# RoboCore_RGB_Sensor.net
KiCad netlist of a schematic drawn in EAGLE
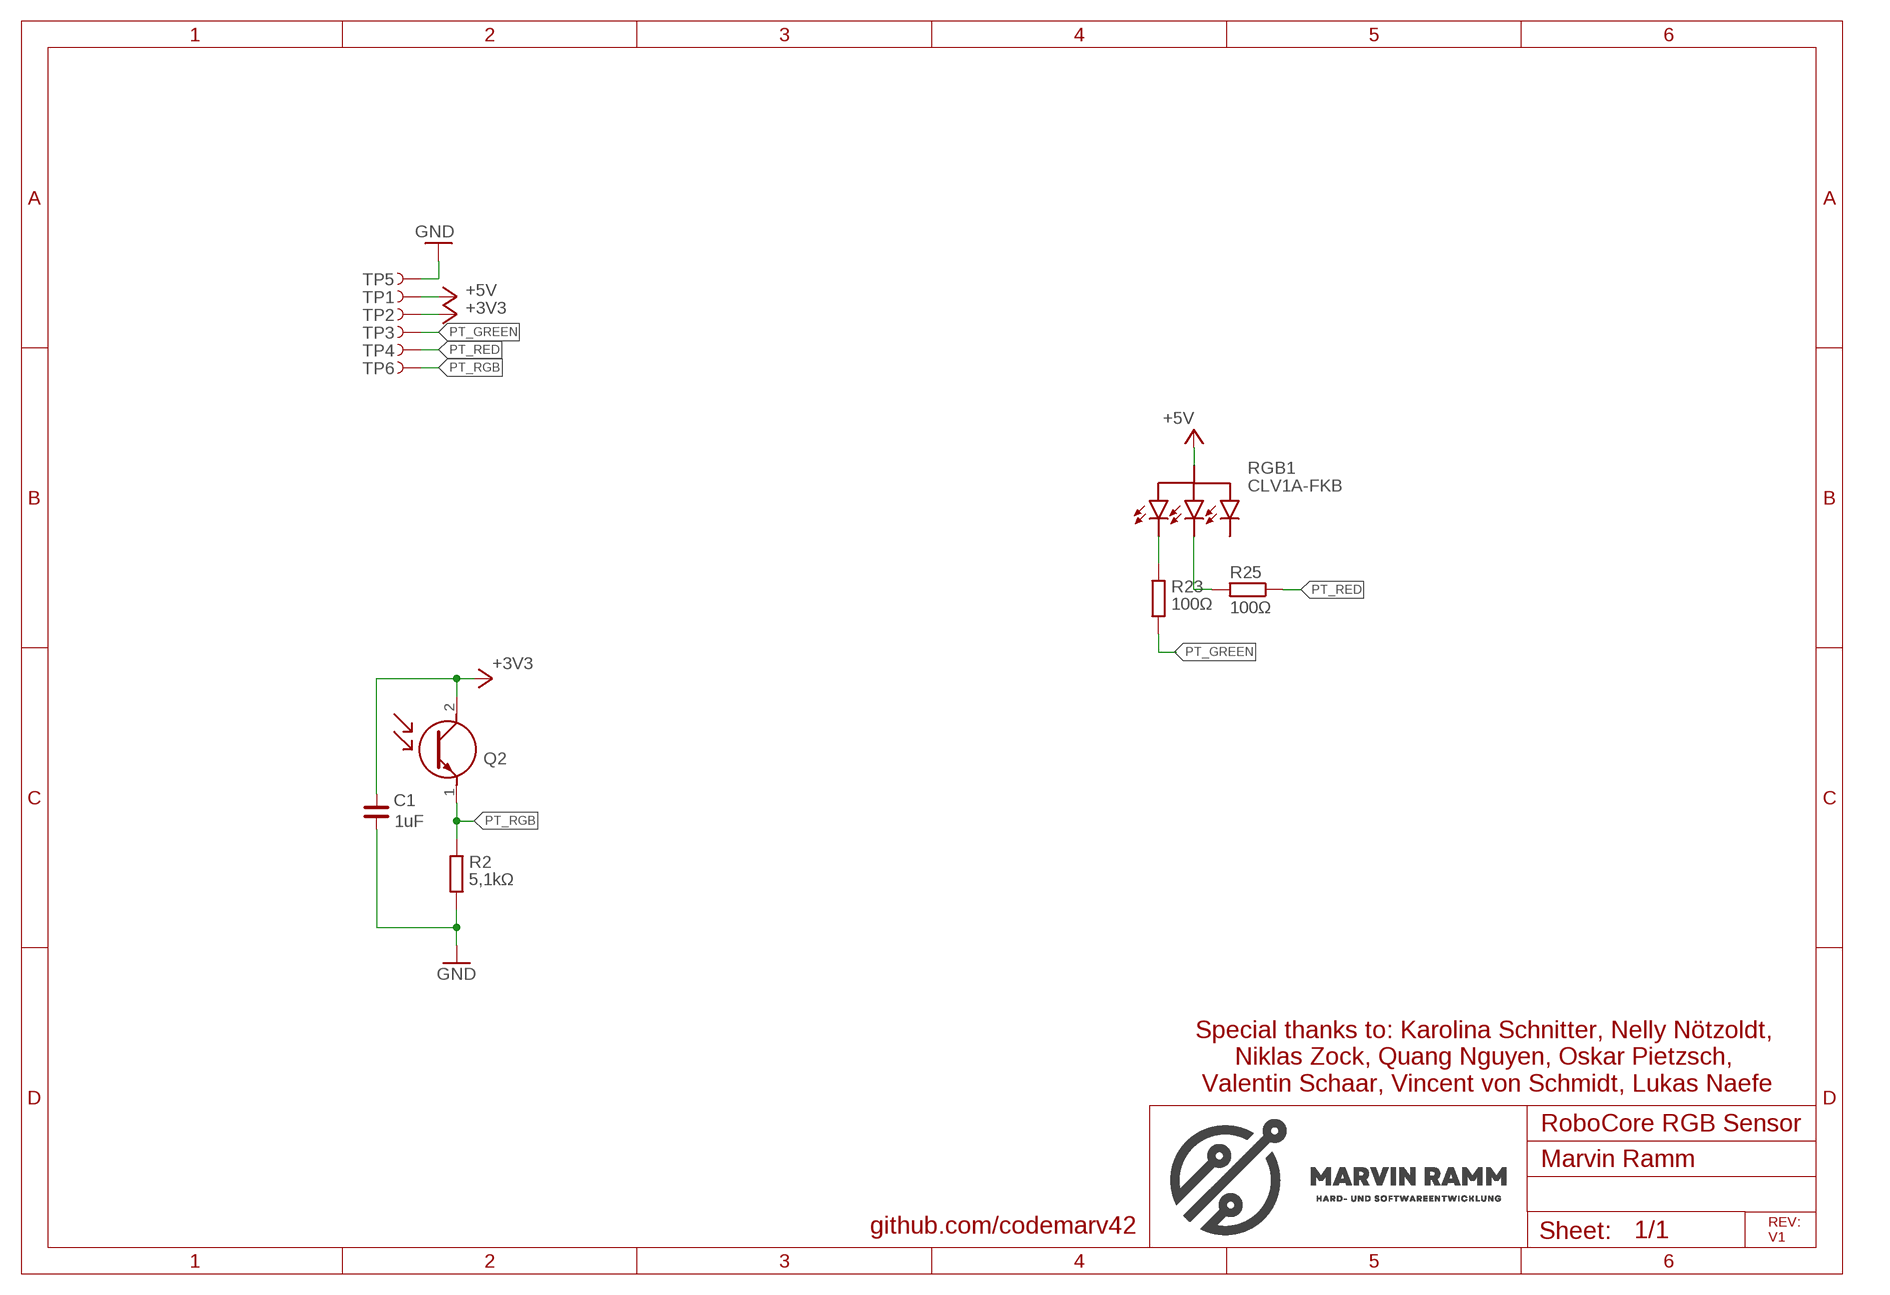
[diagram p0: schematic, sheet 1]

(export (version "E")
  (design (tool "Eeschema 10.0.6"))
  (components
    (comp (ref "C1")
      (value "1uF")
      (footprint "eagle-import:C0402")
      (libsource (lib "eagle-import") (part "C_0402"))
    )
    (comp (ref "Q2")
      (value "PT17-21C/L41/TR8")
      (footprint "eagle-import:0805")
      (libsource (lib "eagle-import") (part "PT17-21C/L41/TR8"))
    )
    (comp (ref "R2")
      (value "5,1kΩ")
      (footprint "eagle-import:R0402")
      (libsource (lib "eagle-import") (part "R_0402"))
    )
    (comp (ref "R23")
      (value "100Ω")
      (footprint "eagle-import:R0402")
      (libsource (lib "eagle-import") (part "R_0402"))
    )
    (comp (ref "R25")
      (value "100Ω")
      (footprint "eagle-import:R0402")
      (libsource (lib "eagle-import") (part "R_0402"))
    )
    (comp (ref "RGB1")
      (value "RGBLED")
      (footprint "eagle-import:RGBLED")
      (libsource (lib "eagle-import") (part "RGBLED"))
    )
    (comp (ref "TP1")
      (value "TEST-POINT3X5")
      (footprint "eagle-import:PAD.03X.05")
      (libsource (lib "eagle-import") (part "TEST-POINT3X5"))
    )
    (comp (ref "TP2")
      (value "TEST-POINT3X5")
      (footprint "eagle-import:PAD.03X.05")
      (libsource (lib "eagle-import") (part "TEST-POINT3X5"))
    )
    (comp (ref "TP3")
      (value "TEST-POINT3X5")
      (footprint "eagle-import:PAD.03X.05")
      (libsource (lib "eagle-import") (part "TEST-POINT3X5"))
    )
    (comp (ref "TP4")
      (value "TEST-POINT3X5")
      (footprint "eagle-import:PAD.03X.05")
      (libsource (lib "eagle-import") (part "TEST-POINT3X5"))
    )
    (comp (ref "TP5")
      (value "TEST-POINT3X5")
      (footprint "eagle-import:PAD.03X.05")
      (libsource (lib "eagle-import") (part "TEST-POINT3X5"))
    )
    (comp (ref "TP6")
      (value "TEST-POINT3X5")
      (footprint "eagle-import:PAD.03X.05")
      (libsource (lib "eagle-import") (part "TEST-POINT3X5"))
    )
  )
  (nets
    (net (code "1") (name "+3V3") (class "Default")
      (node (ref "C1") (pin "2") (pinfunction "2_2") (pintype "passive"))
      (node (ref "Q2") (pin "2") (pinfunction "C_2") (pintype "bidirectional"))
      (node (ref "TP2") (pin "1") (pinfunction "1_1") (pintype "bidirectional"))
    )
    (net (code "2") (name "+5V") (class "Default")
      (node (ref "RGB1") (pin "+5V") (pinfunction "+5V_+5V") (pintype "bidirectional"))
      (node (ref "TP1") (pin "1") (pinfunction "1_1") (pintype "bidirectional"))
    )
    (net (code "3") (name "GND") (class "Default")
      (node (ref "C1") (pin "1") (pinfunction "1_1") (pintype "passive"))
      (node (ref "R2") (pin "2") (pinfunction "2_2") (pintype "passive"))
      (node (ref "TP5") (pin "1") (pinfunction "1_1") (pintype "bidirectional"))
    )
    (net (code "4") (name "Net-(R23-Pad1)") (class "Default")
      (node (ref "R23") (pin "1") (pinfunction "1_1") (pintype "passive"))
      (node (ref "RGB1") (pin "P3") (pinfunction "P3_P3") (pintype "bidirectional"))
    )
    (net (code "5") (name "Net-(R25-Pad1)") (class "Default")
      (node (ref "R25") (pin "1") (pinfunction "1_1") (pintype "passive"))
      (node (ref "RGB1") (pin "P2") (pinfunction "P2_P2") (pintype "bidirectional"))
    )
    (net (code "6") (name "PT_GREEN") (class "Default")
      (node (ref "R23") (pin "2") (pinfunction "2_2") (pintype "passive"))
      (node (ref "TP3") (pin "1") (pinfunction "1_1") (pintype "bidirectional"))
    )
    (net (code "7") (name "PT_RED") (class "Default")
      (node (ref "R25") (pin "2") (pinfunction "2_2") (pintype "passive"))
      (node (ref "TP4") (pin "1") (pinfunction "1_1") (pintype "bidirectional"))
    )
    (net (code "8") (name "PT_RGB") (class "Default")
      (node (ref "Q2") (pin "1") (pinfunction "E_1") (pintype "bidirectional"))
      (node (ref "R2") (pin "1") (pinfunction "1_1") (pintype "passive"))
      (node (ref "TP6") (pin "1") (pinfunction "1_1") (pintype "bidirectional"))
    )
    (net (code "9") (name "unconnected-(RGB1-PadP1)") (class "Default")
      (node (ref "RGB1") (pin "P1") (pinfunction "P1_P1") (pintype "bidirectional"))
    )
  )
)
